# QSTL_RFSW_LED.net
KiCad netlist of a schematic drawn in Altium Designer
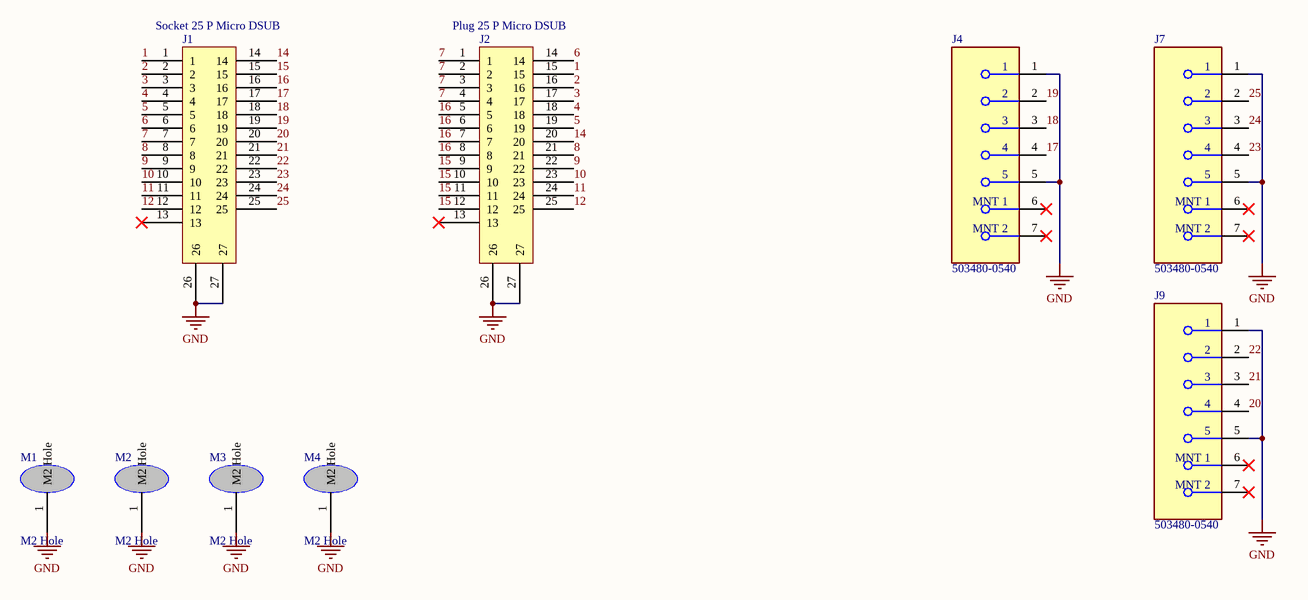
[diagram p0: QSTL_RFSW_LED.SchDoc]

(export (version "E")
  (design (tool "Eeschema 10.0.6"))
  (components
    (comp (ref "J1")
      (value "Socket 25 P Micro DSUB")
      (footprint "581-M25-213L461")
      (libsource (lib "QSTL_MicroDSUB_FFC") (part "581-M25-213L461"))
    )
    (comp (ref "J2")
      (value "Plug 25 P Micro DSUB")
      (footprint "581-M25-113L461")
      (libsource (lib "QSTL_RFSW_LED") (part "581-M25-113L461"))
    )
    (comp (ref "J4")
      (value "503480-0540")
      (footprint "FP-503480-0540-MFG")
      (description "503480-0540 Connector FFC/FPC SKT 5 Position 0.5mm Solder Right Angle Surface Mount T/R")
      (libsource (lib "Altium Content Vault") (part "6b037d2877ced340e1c65ac82253790"))
    )
    (comp (ref "J7")
      (value "503480-0540")
      (footprint "FP-503480-0540-MFG")
      (description "503480-0540 Connector FFC/FPC SKT 5 Position 0.5mm Solder Right Angle Surface Mount T/R")
      (libsource (lib "Altium Content Vault") (part "6b037d2877ced340e1c65ac82253790"))
    )
    (comp (ref "J9")
      (value "503480-0540")
      (footprint "FP-503480-0540-MFG")
      (description "503480-0540 Connector FFC/FPC SKT 5 Position 0.5mm Solder Right Angle Surface Mount T/R")
      (libsource (lib "Altium Content Vault") (part "6b037d2877ced340e1c65ac82253790"))
    )
    (comp (ref "M1")
      (value "M2 Hole")
      (footprint "M2_Hole")
      (libsource (lib "QSTL_MicroDSUB_FFC") (part "M2_HOLE"))
    )
    (comp (ref "M2")
      (value "M2 Hole")
      (footprint "M2_Hole")
      (libsource (lib "QSTL_MicroDSUB_FFC") (part "M2_HOLE"))
    )
    (comp (ref "M3")
      (value "M2 Hole")
      (footprint "M2_Hole")
      (libsource (lib "QSTL_MicroDSUB_FFC") (part "M2_HOLE"))
    )
    (comp (ref "M4")
      (value "M2 Hole")
      (footprint "M2_Hole")
      (libsource (lib "QSTL_MicroDSUB_FFC") (part "M2_HOLE"))
    )
  )
  (nets
    (net (code "1") (name "/1") (class "Default")
      (node (ref "J1") (pin "1") (pinfunction "1_1") (pintype "passive"))
      (node (ref "J2") (pin "15") (pinfunction "15_15") (pintype "passive"))
    )
    (net (code "2") (name "/2") (class "Default")
      (node (ref "J1") (pin "2") (pinfunction "2_2") (pintype "passive"))
      (node (ref "J2") (pin "16") (pinfunction "16_16") (pintype "passive"))
    )
    (net (code "3") (name "/3") (class "Default")
      (node (ref "J1") (pin "3") (pinfunction "3_3") (pintype "passive"))
      (node (ref "J2") (pin "17") (pinfunction "17_17") (pintype "passive"))
    )
    (net (code "4") (name "/4") (class "Default")
      (node (ref "J1") (pin "4") (pinfunction "4_4") (pintype "passive"))
      (node (ref "J2") (pin "18") (pinfunction "18_18") (pintype "passive"))
    )
    (net (code "5") (name "/5") (class "Default")
      (node (ref "J1") (pin "5") (pinfunction "5_5") (pintype "passive"))
      (node (ref "J2") (pin "19") (pinfunction "19_19") (pintype "passive"))
    )
    (net (code "6") (name "/6") (class "Default")
      (node (ref "J1") (pin "6") (pinfunction "6_6") (pintype "passive"))
      (node (ref "J2") (pin "14") (pinfunction "14_14") (pintype "passive"))
    )
    (net (code "7") (name "/7") (class "Default")
      (node (ref "J1") (pin "7") (pinfunction "7_7") (pintype "passive"))
      (node (ref "J2") (pin "1") (pinfunction "1_1") (pintype "passive"))
      (node (ref "J2") (pin "2") (pinfunction "2_2") (pintype "passive"))
      (node (ref "J2") (pin "3") (pinfunction "3_3") (pintype "passive"))
      (node (ref "J2") (pin "4") (pinfunction "4_4") (pintype "passive"))
    )
    (net (code "8") (name "/8") (class "Default")
      (node (ref "J1") (pin "8") (pinfunction "8_8") (pintype "passive"))
      (node (ref "J2") (pin "21") (pinfunction "21_21") (pintype "passive"))
    )
    (net (code "9") (name "/9") (class "Default")
      (node (ref "J1") (pin "9") (pinfunction "9_9") (pintype "passive"))
      (node (ref "J2") (pin "22") (pinfunction "22_22") (pintype "passive"))
    )
    (net (code "10") (name "/10") (class "Default")
      (node (ref "J1") (pin "10") (pinfunction "10_10") (pintype "passive"))
      (node (ref "J2") (pin "23") (pinfunction "23_23") (pintype "passive"))
    )
    (net (code "11") (name "/11") (class "Default")
      (node (ref "J1") (pin "11") (pinfunction "11_11") (pintype "passive"))
      (node (ref "J2") (pin "24") (pinfunction "24_24") (pintype "passive"))
    )
    (net (code "12") (name "/12") (class "Default")
      (node (ref "J1") (pin "12") (pinfunction "12_12") (pintype "passive"))
      (node (ref "J2") (pin "25") (pinfunction "25_25") (pintype "passive"))
    )
    (net (code "13") (name "/14") (class "Default")
      (node (ref "J1") (pin "14") (pinfunction "14_14") (pintype "passive"))
      (node (ref "J2") (pin "20") (pinfunction "20_20") (pintype "passive"))
    )
    (net (code "14") (name "/15") (class "Default")
      (node (ref "J1") (pin "15") (pinfunction "15_15") (pintype "passive"))
      (node (ref "J2") (pin "10") (pinfunction "10_10") (pintype "passive"))
      (node (ref "J2") (pin "11") (pinfunction "11_11") (pintype "passive"))
      (node (ref "J2") (pin "12") (pinfunction "12_12") (pintype "passive"))
      (node (ref "J2") (pin "9") (pinfunction "9_9") (pintype "passive"))
    )
    (net (code "15") (name "/16") (class "Default")
      (node (ref "J1") (pin "16") (pinfunction "16_16") (pintype "passive"))
      (node (ref "J2") (pin "5") (pinfunction "5_5") (pintype "passive"))
      (node (ref "J2") (pin "6") (pinfunction "6_6") (pintype "passive"))
      (node (ref "J2") (pin "7") (pinfunction "7_7") (pintype "passive"))
      (node (ref "J2") (pin "8") (pinfunction "8_8") (pintype "passive"))
    )
    (net (code "16") (name "/17") (class "Default")
      (node (ref "J1") (pin "17") (pinfunction "17_17") (pintype "passive"))
      (node (ref "J4") (pin "4") (pinfunction "4_4") (pintype "passive"))
    )
    (net (code "17") (name "/18") (class "Default")
      (node (ref "J1") (pin "18") (pinfunction "18_18") (pintype "passive"))
      (node (ref "J4") (pin "3") (pinfunction "3_3") (pintype "passive"))
    )
    (net (code "18") (name "/19") (class "Default")
      (node (ref "J1") (pin "19") (pinfunction "19_19") (pintype "passive"))
      (node (ref "J4") (pin "2") (pinfunction "2_2") (pintype "passive"))
    )
    (net (code "19") (name "/20") (class "Default")
      (node (ref "J1") (pin "20") (pinfunction "20_20") (pintype "passive"))
      (node (ref "J9") (pin "4") (pinfunction "4_4") (pintype "passive"))
    )
    (net (code "20") (name "/21") (class "Default")
      (node (ref "J1") (pin "21") (pinfunction "21_21") (pintype "passive"))
      (node (ref "J9") (pin "3") (pinfunction "3_3") (pintype "passive"))
    )
    (net (code "21") (name "/22") (class "Default")
      (node (ref "J1") (pin "22") (pinfunction "22_22") (pintype "passive"))
      (node (ref "J9") (pin "2") (pinfunction "2_2") (pintype "passive"))
    )
    (net (code "22") (name "/23") (class "Default")
      (node (ref "J1") (pin "23") (pinfunction "23_23") (pintype "passive"))
      (node (ref "J7") (pin "4") (pinfunction "4_4") (pintype "passive"))
    )
    (net (code "23") (name "/24") (class "Default")
      (node (ref "J1") (pin "24") (pinfunction "24_24") (pintype "passive"))
      (node (ref "J7") (pin "3") (pinfunction "3_3") (pintype "passive"))
    )
    (net (code "24") (name "/25") (class "Default")
      (node (ref "J1") (pin "25") (pinfunction "25_25") (pintype "passive"))
      (node (ref "J7") (pin "2") (pinfunction "2_2") (pintype "passive"))
    )
    (net (code "25") (name "GND") (class "Default")
      (node (ref "J1") (pin "26") (pinfunction "26_26") (pintype "passive"))
      (node (ref "J1") (pin "27") (pinfunction "27_27") (pintype "passive"))
      (node (ref "J2") (pin "26") (pinfunction "26_26") (pintype "passive"))
      (node (ref "J2") (pin "27") (pinfunction "27_27") (pintype "passive"))
      (node (ref "J4") (pin "1") (pinfunction "1_1") (pintype "passive"))
      (node (ref "J4") (pin "5") (pinfunction "5_5") (pintype "passive"))
      (node (ref "J7") (pin "1") (pinfunction "1_1") (pintype "passive"))
      (node (ref "J7") (pin "5") (pinfunction "5_5") (pintype "passive"))
      (node (ref "J9") (pin "1") (pinfunction "1_1") (pintype "passive"))
      (node (ref "J9") (pin "5") (pinfunction "5_5") (pintype "passive"))
      (node (ref "M1") (pin "1") (pinfunction "M2_Hole_1") (pintype "passive"))
      (node (ref "M2") (pin "1") (pinfunction "M2_Hole_1") (pintype "passive"))
      (node (ref "M3") (pin "1") (pinfunction "M2_Hole_1") (pintype "passive"))
      (node (ref "M4") (pin "1") (pinfunction "M2_Hole_1") (pintype "passive"))
    )
    (net (code "26") (name "unconnected-(J1-Pad13)") (class "Default")
      (node (ref "J1") (pin "13") (pinfunction "13_13") (pintype "passive+no_connect"))
    )
    (net (code "27") (name "unconnected-(J2-Pad13)") (class "Default")
      (node (ref "J2") (pin "13") (pinfunction "13_13") (pintype "passive+no_connect"))
    )
    (net (code "28") (name "unconnected-(J4-MNT_1-Pad6)") (class "Default")
      (node (ref "J4") (pin "6") (pinfunction "MNT_1_6") (pintype "passive+no_connect"))
    )
    (net (code "29") (name "unconnected-(J4-MNT_2-Pad7)") (class "Default")
      (node (ref "J4") (pin "7") (pinfunction "MNT_2_7") (pintype "passive+no_connect"))
    )
    (net (code "30") (name "unconnected-(J7-MNT_1-Pad6)") (class "Default")
      (node (ref "J7") (pin "6") (pinfunction "MNT_1_6") (pintype "passive+no_connect"))
    )
    (net (code "31") (name "unconnected-(J7-MNT_2-Pad7)") (class "Default")
      (node (ref "J7") (pin "7") (pinfunction "MNT_2_7") (pintype "passive+no_connect"))
    )
    (net (code "32") (name "unconnected-(J9-MNT_1-Pad6)") (class "Default")
      (node (ref "J9") (pin "6") (pinfunction "MNT_1_6") (pintype "passive+no_connect"))
    )
    (net (code "33") (name "unconnected-(J9-MNT_2-Pad7)") (class "Default")
      (node (ref "J9") (pin "7") (pinfunction "MNT_2_7") (pintype "passive+no_connect"))
    )
  )
)
